# P-LED-0004-V1A_EAGLE_Schematic.net
KiCad netlist of a schematic drawn in EAGLE
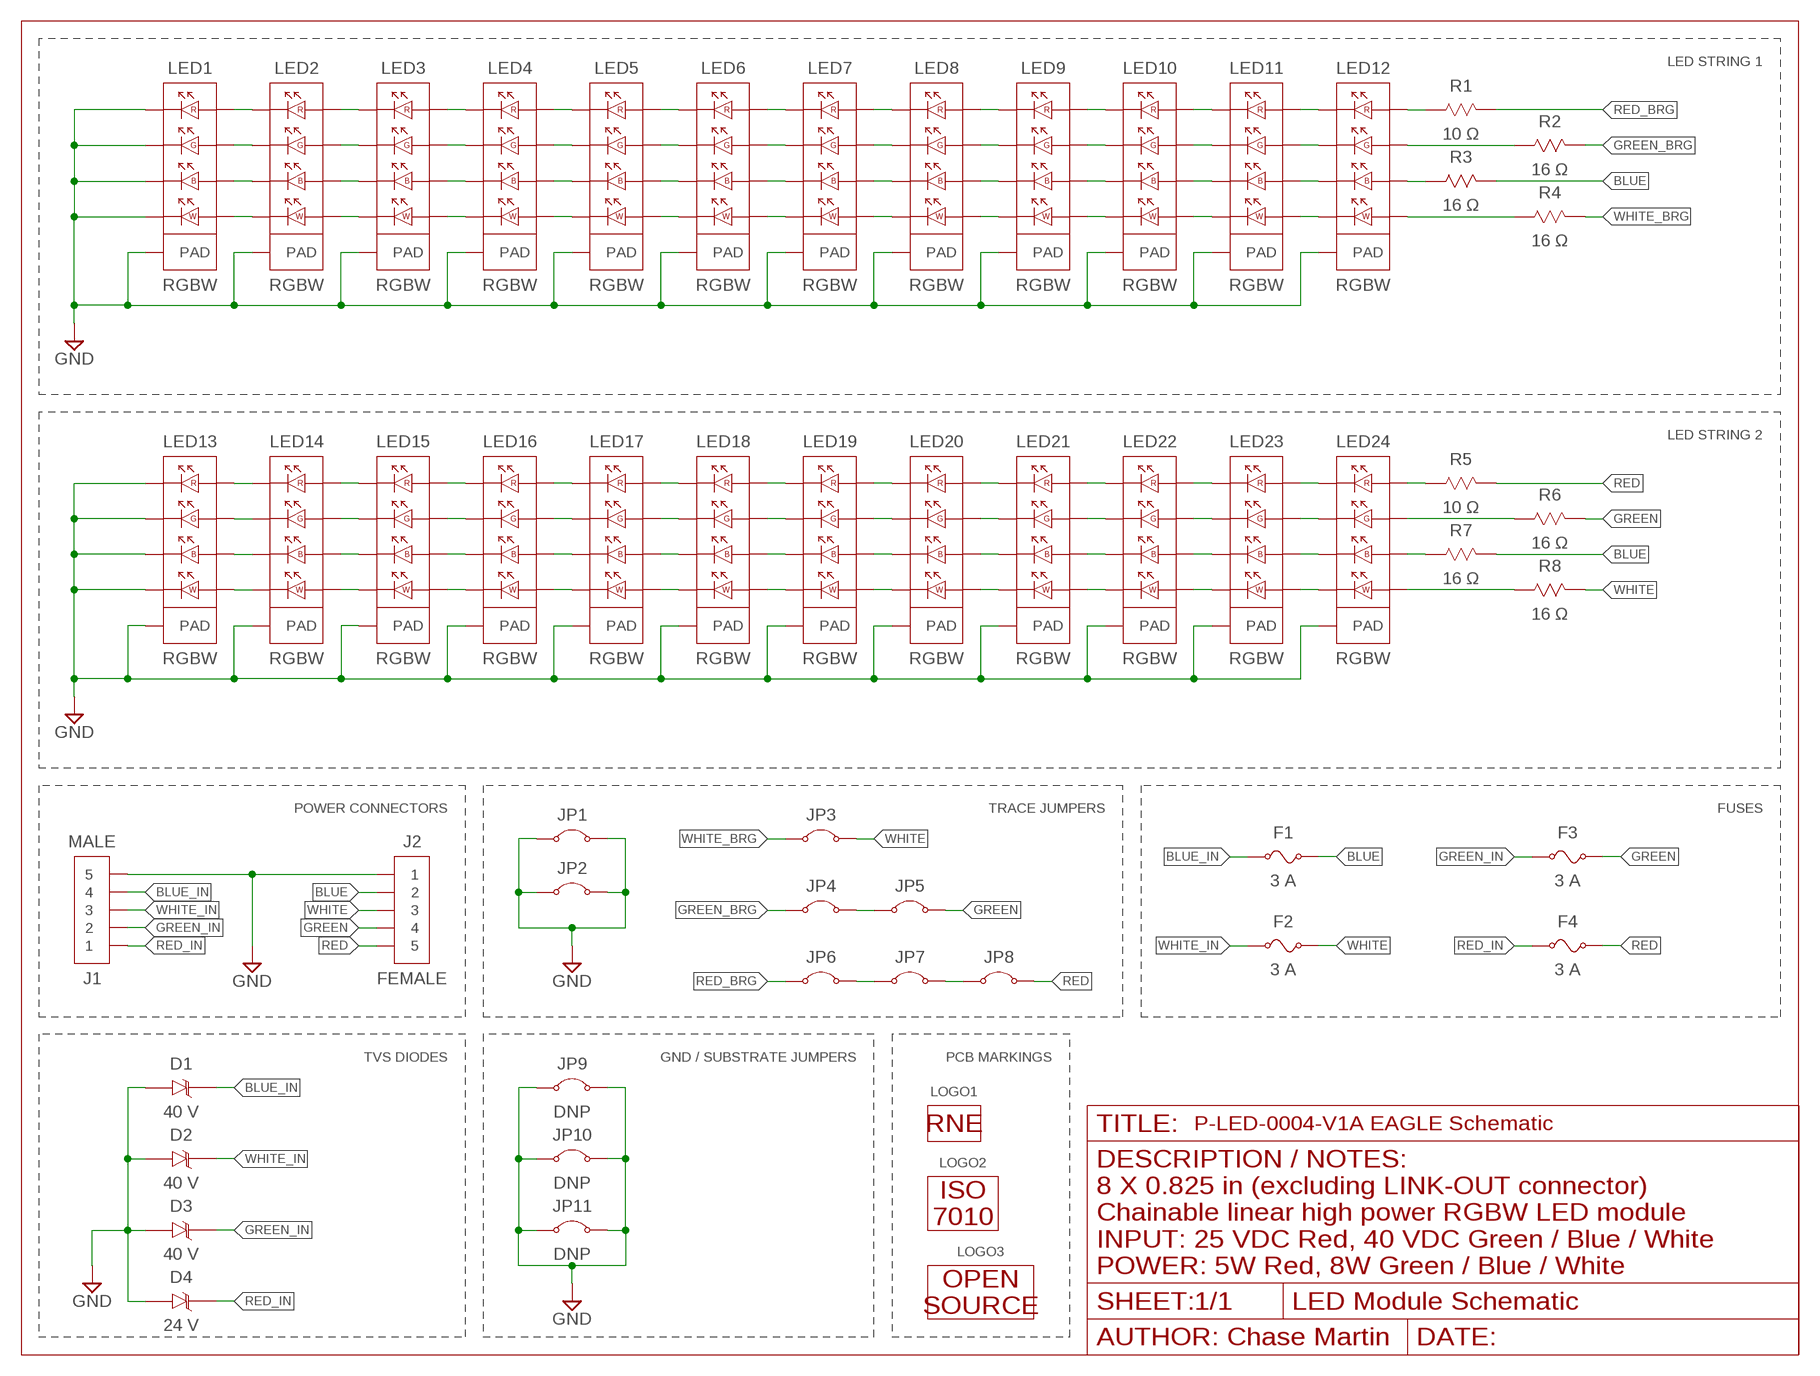
[diagram p0: schematic, sheet 1]

(export (version "E")
  (design (tool "Eeschema 10.0.6"))
  (components
    (comp (ref "D1")
      (value "40 V")
      (footprint "eagle-import:0603_POLARIZED")
      (libsource (lib "eagle-import") (part "UNIDIRECTIONAL_TVS_DIODESMD_0603"))
    )
    (comp (ref "D2")
      (value "40 V")
      (footprint "eagle-import:0603_POLARIZED")
      (libsource (lib "eagle-import") (part "UNIDIRECTIONAL_TVS_DIODESMD_0603"))
    )
    (comp (ref "D3")
      (value "40 V")
      (footprint "eagle-import:0603_POLARIZED")
      (libsource (lib "eagle-import") (part "UNIDIRECTIONAL_TVS_DIODESMD_0603"))
    )
    (comp (ref "D4")
      (value "24 V")
      (footprint "eagle-import:0603_POLARIZED")
      (libsource (lib "eagle-import") (part "UNIDIRECTIONAL_TVS_DIODESMD_0603"))
    )
    (comp (ref "F1")
      (value "3 A")
      (footprint "eagle-import:1206")
      (libsource (lib "eagle-import") (part "FUSESMD_1206"))
    )
    (comp (ref "F2")
      (value "3 A")
      (footprint "eagle-import:1206")
      (libsource (lib "eagle-import") (part "FUSESMD_1206"))
    )
    (comp (ref "F3")
      (value "3 A")
      (footprint "eagle-import:1206")
      (libsource (lib "eagle-import") (part "FUSESMD_1206"))
    )
    (comp (ref "F4")
      (value "3 A")
      (footprint "eagle-import:1206")
      (libsource (lib "eagle-import") (part "FUSESMD_1206"))
    )
    (comp (ref "J1")
      (value "MALE")
      (footprint "eagle-import:5-PIN_1-ROW_MALE_SMD_HORIZONTAL")
      (libsource (lib "eagle-import") (part "5-PIN_1-ROWMALE_SMD_HORIZONTAL"))
    )
    (comp (ref "J2")
      (value "FEMALE")
      (footprint "eagle-import:5-PIN_1-ROW_FEMALE_SMD_HORIZONTAL")
      (libsource (lib "eagle-import") (part "5-PIN_1-ROWFEMALE_SMD_HORIZONTAL"))
    )
    (comp (ref "JP1")
      (value "JUMPERSMD_1206")
      (footprint "eagle-import:1206")
      (libsource (lib "eagle-import") (part "JUMPERSMD_1206"))
    )
    (comp (ref "JP2")
      (value "JUMPERSMD_1206")
      (footprint "eagle-import:1206")
      (libsource (lib "eagle-import") (part "JUMPERSMD_1206"))
    )
    (comp (ref "JP3")
      (value "JUMPERSMD_1206")
      (footprint "eagle-import:1206")
      (libsource (lib "eagle-import") (part "JUMPERSMD_1206"))
    )
    (comp (ref "JP4")
      (value "JUMPERSMD_1206")
      (footprint "eagle-import:1206")
      (libsource (lib "eagle-import") (part "JUMPERSMD_1206"))
    )
    (comp (ref "JP5")
      (value "JUMPERSMD_1206")
      (footprint "eagle-import:1206")
      (libsource (lib "eagle-import") (part "JUMPERSMD_1206"))
    )
    (comp (ref "JP6")
      (value "JUMPERSMD_1206")
      (footprint "eagle-import:1206")
      (libsource (lib "eagle-import") (part "JUMPERSMD_1206"))
    )
    (comp (ref "JP7")
      (value "JUMPERSMD_1206")
      (footprint "eagle-import:1206")
      (libsource (lib "eagle-import") (part "JUMPERSMD_1206"))
    )
    (comp (ref "JP8")
      (value "JUMPERSMD_1206")
      (footprint "eagle-import:1206")
      (libsource (lib "eagle-import") (part "JUMPERSMD_1206"))
    )
    (comp (ref "JP9")
      (value "DNP")
      (footprint "eagle-import:0603")
      (libsource (lib "eagle-import") (part "JUMPERSMD_0603"))
    )
    (comp (ref "JP10")
      (value "DNP")
      (footprint "eagle-import:0603")
      (libsource (lib "eagle-import") (part "JUMPERSMD_0603"))
    )
    (comp (ref "JP11")
      (value "DNP")
      (footprint "eagle-import:0603")
      (libsource (lib "eagle-import") (part "JUMPERSMD_0603"))
    )
    (comp (ref "LED1")
      (value "RGBW")
      (footprint "eagle-import:IN-P55QSTGRGBW_AIS")
      (libsource (lib "eagle-import") (part "IN-P55QSTGRGBWAIS"))
    )
    (comp (ref "LED2")
      (value "RGBW")
      (footprint "eagle-import:IN-P55QSTGRGBW_AIS")
      (libsource (lib "eagle-import") (part "IN-P55QSTGRGBWAIS"))
    )
    (comp (ref "LED3")
      (value "RGBW")
      (footprint "eagle-import:IN-P55QSTGRGBW_AIS")
      (libsource (lib "eagle-import") (part "IN-P55QSTGRGBWAIS"))
    )
    (comp (ref "LED4")
      (value "RGBW")
      (footprint "eagle-import:IN-P55QSTGRGBW_AIS")
      (libsource (lib "eagle-import") (part "IN-P55QSTGRGBWAIS"))
    )
    (comp (ref "LED5")
      (value "RGBW")
      (footprint "eagle-import:IN-P55QSTGRGBW_AIS")
      (libsource (lib "eagle-import") (part "IN-P55QSTGRGBWAIS"))
    )
    (comp (ref "LED6")
      (value "RGBW")
      (footprint "eagle-import:IN-P55QSTGRGBW_AIS")
      (libsource (lib "eagle-import") (part "IN-P55QSTGRGBWAIS"))
    )
    (comp (ref "LED7")
      (value "RGBW")
      (footprint "eagle-import:IN-P55QSTGRGBW_AIS")
      (libsource (lib "eagle-import") (part "IN-P55QSTGRGBWAIS"))
    )
    (comp (ref "LED8")
      (value "RGBW")
      (footprint "eagle-import:IN-P55QSTGRGBW_AIS")
      (libsource (lib "eagle-import") (part "IN-P55QSTGRGBWAIS"))
    )
    (comp (ref "LED9")
      (value "RGBW")
      (footprint "eagle-import:IN-P55QSTGRGBW_AIS")
      (libsource (lib "eagle-import") (part "IN-P55QSTGRGBWAIS"))
    )
    (comp (ref "LED10")
      (value "RGBW")
      (footprint "eagle-import:IN-P55QSTGRGBW_AIS")
      (libsource (lib "eagle-import") (part "IN-P55QSTGRGBWAIS"))
    )
    (comp (ref "LED11")
      (value "RGBW")
      (footprint "eagle-import:IN-P55QSTGRGBW_AIS")
      (libsource (lib "eagle-import") (part "IN-P55QSTGRGBWAIS"))
    )
    (comp (ref "LED12")
      (value "RGBW")
      (footprint "eagle-import:IN-P55QSTGRGBW_AIS")
      (libsource (lib "eagle-import") (part "IN-P55QSTGRGBWAIS"))
    )
    (comp (ref "LED13")
      (value "RGBW")
      (footprint "eagle-import:IN-P55QSTGRGBW_AIS")
      (libsource (lib "eagle-import") (part "IN-P55QSTGRGBWAIS"))
    )
    (comp (ref "LED14")
      (value "RGBW")
      (footprint "eagle-import:IN-P55QSTGRGBW_AIS")
      (libsource (lib "eagle-import") (part "IN-P55QSTGRGBWAIS"))
    )
    (comp (ref "LED15")
      (value "RGBW")
      (footprint "eagle-import:IN-P55QSTGRGBW_AIS")
      (libsource (lib "eagle-import") (part "IN-P55QSTGRGBWAIS"))
    )
    (comp (ref "LED16")
      (value "RGBW")
      (footprint "eagle-import:IN-P55QSTGRGBW_AIS")
      (libsource (lib "eagle-import") (part "IN-P55QSTGRGBWAIS"))
    )
    (comp (ref "LED17")
      (value "RGBW")
      (footprint "eagle-import:IN-P55QSTGRGBW_AIS")
      (libsource (lib "eagle-import") (part "IN-P55QSTGRGBWAIS"))
    )
    (comp (ref "LED18")
      (value "RGBW")
      (footprint "eagle-import:IN-P55QSTGRGBW_AIS")
      (libsource (lib "eagle-import") (part "IN-P55QSTGRGBWAIS"))
    )
    (comp (ref "LED19")
      (value "RGBW")
      (footprint "eagle-import:IN-P55QSTGRGBW_AIS")
      (libsource (lib "eagle-import") (part "IN-P55QSTGRGBWAIS"))
    )
    (comp (ref "LED20")
      (value "RGBW")
      (footprint "eagle-import:IN-P55QSTGRGBW_AIS")
      (libsource (lib "eagle-import") (part "IN-P55QSTGRGBWAIS"))
    )
    (comp (ref "LED21")
      (value "RGBW")
      (footprint "eagle-import:IN-P55QSTGRGBW_AIS")
      (libsource (lib "eagle-import") (part "IN-P55QSTGRGBWAIS"))
    )
    (comp (ref "LED22")
      (value "RGBW")
      (footprint "eagle-import:IN-P55QSTGRGBW_AIS")
      (libsource (lib "eagle-import") (part "IN-P55QSTGRGBWAIS"))
    )
    (comp (ref "LED23")
      (value "RGBW")
      (footprint "eagle-import:IN-P55QSTGRGBW_AIS")
      (libsource (lib "eagle-import") (part "IN-P55QSTGRGBWAIS"))
    )
    (comp (ref "LED24")
      (value "RGBW")
      (footprint "eagle-import:IN-P55QSTGRGBW_AIS")
      (libsource (lib "eagle-import") (part "IN-P55QSTGRGBWAIS"))
    )
    (comp (ref "LOGO1")
      (value "PROFILE_LOGO_RNE0.375\"")
      (footprint "eagle-import:RNE_PROFILE-LOGO_375")
      (libsource (lib "eagle-import") (part "PROFILE_LOGO_RNE0.375{dblquote}"))
    )
    (comp (ref "LOGO2")
      (value "HOT_SURFACE_ISO0.375\"_LABEL")
      (footprint "eagle-import:ISO_HOT-SURFACE_375_LABEL")
      (libsource (lib "eagle-import") (part "HOT_SURFACE_ISO0.375{dblquote}_LABEL"))
    )
    (comp (ref "LOGO3")
      (value "OPEN_SOURCE_OSHWA0.375\"_LABEL")
      (footprint "eagle-import:OSHWA_OPEN-SOURCE_375_LABEL")
      (libsource (lib "eagle-import") (part "OPEN_SOURCE_OSHWA0.375{dblquote}_LABEL"))
    )
    (comp (ref "R1")
      (value "10 Ω")
      (footprint "eagle-import:0603")
      (libsource (lib "eagle-import") (part "RESISTORSMD_0603"))
    )
    (comp (ref "R2")
      (value "16 Ω")
      (footprint "eagle-import:0603")
      (libsource (lib "eagle-import") (part "RESISTORSMD_0603"))
    )
    (comp (ref "R3")
      (value "16 Ω")
      (footprint "eagle-import:0603")
      (libsource (lib "eagle-import") (part "RESISTORSMD_0603"))
    )
    (comp (ref "R4")
      (value "16 Ω")
      (footprint "eagle-import:0603")
      (libsource (lib "eagle-import") (part "RESISTORSMD_0603"))
    )
    (comp (ref "R5")
      (value "10 Ω")
      (footprint "eagle-import:0603")
      (libsource (lib "eagle-import") (part "RESISTORSMD_0603"))
    )
    (comp (ref "R6")
      (value "16 Ω")
      (footprint "eagle-import:0603")
      (libsource (lib "eagle-import") (part "RESISTORSMD_0603"))
    )
    (comp (ref "R7")
      (value "16 Ω")
      (footprint "eagle-import:0603")
      (libsource (lib "eagle-import") (part "RESISTORSMD_0603"))
    )
    (comp (ref "R8")
      (value "16 Ω")
      (footprint "eagle-import:0603")
      (libsource (lib "eagle-import") (part "RESISTORSMD_0603"))
    )
  )
  (nets
    (net (code "1") (name "BLUE") (class "Default")
      (node (ref "F1") (pin "2") (pinfunction "2_2") (pintype "passive"))
      (node (ref "J2") (pin "2") (pinfunction "2_2") (pintype "passive"))
      (node (ref "R3") (pin "2") (pinfunction "2_2") (pintype "passive"))
      (node (ref "R7") (pin "2") (pinfunction "2_2") (pintype "passive"))
    )
    (net (code "2") (name "BLUE_IN") (class "Default")
      (node (ref "D1") (pin "K") (pinfunction "K_K") (pintype "passive"))
      (node (ref "F1") (pin "1") (pinfunction "1_1") (pintype "passive"))
      (node (ref "J1") (pin "4") (pinfunction "4_4") (pintype "passive"))
    )
    (net (code "3") (name "GND") (class "Default")
      (node (ref "D1") (pin "A") (pinfunction "A_A") (pintype "passive"))
      (node (ref "D2") (pin "A") (pinfunction "A_A") (pintype "passive"))
      (node (ref "D3") (pin "A") (pinfunction "A_A") (pintype "passive"))
      (node (ref "D4") (pin "A") (pinfunction "A_A") (pintype "passive"))
      (node (ref "J1") (pin "5") (pinfunction "5_5") (pintype "passive"))
      (node (ref "J2") (pin "1") (pinfunction "1_1") (pintype "passive"))
      (node (ref "JP1") (pin "1") (pinfunction "1_1") (pintype "passive"))
      (node (ref "JP1") (pin "2") (pinfunction "2_2") (pintype "passive"))
      (node (ref "JP10") (pin "1") (pinfunction "1_1") (pintype "passive"))
      (node (ref "JP10") (pin "2") (pinfunction "2_2") (pintype "passive"))
      (node (ref "JP11") (pin "1") (pinfunction "1_1") (pintype "passive"))
      (node (ref "JP11") (pin "2") (pinfunction "2_2") (pintype "passive"))
      (node (ref "JP2") (pin "1") (pinfunction "1_1") (pintype "passive"))
      (node (ref "JP2") (pin "2") (pinfunction "2_2") (pintype "passive"))
      (node (ref "JP9") (pin "1") (pinfunction "1_1") (pintype "passive"))
      (node (ref "JP9") (pin "2") (pinfunction "2_2") (pintype "passive"))
      (node (ref "LED1") (pin "BLUE_N") (pinfunction "BLUE_N_BLUE_N") (pintype "output"))
      (node (ref "LED1") (pin "GREEN_N") (pinfunction "GREEN_N_GREEN_N") (pintype "output"))
      (node (ref "LED1") (pin "PAD") (pinfunction "PAD_PAD") (pintype "passive"))
      (node (ref "LED1") (pin "RED_N") (pinfunction "RED_N_RED_N") (pintype "output"))
      (node (ref "LED1") (pin "WHITE_N") (pinfunction "WHITE_N_WHITE_N") (pintype "output"))
      (node (ref "LED10") (pin "PAD") (pinfunction "PAD_PAD") (pintype "passive"))
      (node (ref "LED11") (pin "PAD") (pinfunction "PAD_PAD") (pintype "passive"))
      (node (ref "LED12") (pin "PAD") (pinfunction "PAD_PAD") (pintype "passive"))
      (node (ref "LED13") (pin "BLUE_N") (pinfunction "BLUE_N_BLUE_N") (pintype "output"))
      (node (ref "LED13") (pin "GREEN_N") (pinfunction "GREEN_N_GREEN_N") (pintype "output"))
      (node (ref "LED13") (pin "PAD") (pinfunction "PAD_PAD") (pintype "passive"))
      (node (ref "LED13") (pin "RED_N") (pinfunction "RED_N_RED_N") (pintype "output"))
      (node (ref "LED13") (pin "WHITE_N") (pinfunction "WHITE_N_WHITE_N") (pintype "output"))
      (node (ref "LED14") (pin "PAD") (pinfunction "PAD_PAD") (pintype "passive"))
      (node (ref "LED15") (pin "PAD") (pinfunction "PAD_PAD") (pintype "passive"))
      (node (ref "LED16") (pin "PAD") (pinfunction "PAD_PAD") (pintype "passive"))
      (node (ref "LED17") (pin "PAD") (pinfunction "PAD_PAD") (pintype "passive"))
      (node (ref "LED18") (pin "PAD") (pinfunction "PAD_PAD") (pintype "passive"))
      (node (ref "LED19") (pin "PAD") (pinfunction "PAD_PAD") (pintype "passive"))
      (node (ref "LED2") (pin "PAD") (pinfunction "PAD_PAD") (pintype "passive"))
      (node (ref "LED20") (pin "PAD") (pinfunction "PAD_PAD") (pintype "passive"))
      (node (ref "LED21") (pin "PAD") (pinfunction "PAD_PAD") (pintype "passive"))
      (node (ref "LED22") (pin "PAD") (pinfunction "PAD_PAD") (pintype "passive"))
      (node (ref "LED23") (pin "PAD") (pinfunction "PAD_PAD") (pintype "passive"))
      (node (ref "LED24") (pin "PAD") (pinfunction "PAD_PAD") (pintype "passive"))
      (node (ref "LED3") (pin "PAD") (pinfunction "PAD_PAD") (pintype "passive"))
      (node (ref "LED4") (pin "PAD") (pinfunction "PAD_PAD") (pintype "passive"))
      (node (ref "LED5") (pin "PAD") (pinfunction "PAD_PAD") (pintype "passive"))
      (node (ref "LED6") (pin "PAD") (pinfunction "PAD_PAD") (pintype "passive"))
      (node (ref "LED7") (pin "PAD") (pinfunction "PAD_PAD") (pintype "passive"))
      (node (ref "LED8") (pin "PAD") (pinfunction "PAD_PAD") (pintype "passive"))
      (node (ref "LED9") (pin "PAD") (pinfunction "PAD_PAD") (pintype "passive"))
    )
    (net (code "4") (name "GREEN") (class "Default")
      (node (ref "F3") (pin "2") (pinfunction "2_2") (pintype "passive"))
      (node (ref "J2") (pin "4") (pinfunction "4_4") (pintype "passive"))
      (node (ref "JP5") (pin "2") (pinfunction "2_2") (pintype "passive"))
      (node (ref "R6") (pin "2") (pinfunction "2_2") (pintype "passive"))
    )
    (net (code "5") (name "GREEN_BRG") (class "Default")
      (node (ref "JP4") (pin "1") (pinfunction "1_1") (pintype "passive"))
      (node (ref "R2") (pin "2") (pinfunction "2_2") (pintype "passive"))
    )
    (net (code "6") (name "GREEN_IN") (class "Default")
      (node (ref "D3") (pin "K") (pinfunction "K_K") (pintype "passive"))
      (node (ref "F3") (pin "1") (pinfunction "1_1") (pintype "passive"))
      (node (ref "J1") (pin "2") (pinfunction "2_2") (pintype "passive"))
    )
    (net (code "7") (name "Net-(JP4-Pad2)") (class "Default")
      (node (ref "JP4") (pin "2") (pinfunction "2_2") (pintype "passive"))
      (node (ref "JP5") (pin "1") (pinfunction "1_1") (pintype "passive"))
    )
    (net (code "8") (name "Net-(JP6-Pad2)") (class "Default")
      (node (ref "JP6") (pin "2") (pinfunction "2_2") (pintype "passive"))
      (node (ref "JP7") (pin "1") (pinfunction "1_1") (pintype "passive"))
    )
    (net (code "9") (name "Net-(JP7-Pad2)") (class "Default")
      (node (ref "JP7") (pin "2") (pinfunction "2_2") (pintype "passive"))
      (node (ref "JP8") (pin "1") (pinfunction "1_1") (pintype "passive"))
    )
    (net (code "10") (name "Net-(LED1-PadBLUE_P)") (class "Default")
      (node (ref "LED1") (pin "BLUE_P") (pinfunction "BLUE_P_BLUE_P") (pintype "input"))
      (node (ref "LED2") (pin "BLUE_N") (pinfunction "BLUE_N_BLUE_N") (pintype "output"))
    )
    (net (code "11") (name "Net-(LED1-PadGREEN_P)") (class "Default")
      (node (ref "LED1") (pin "GREEN_P") (pinfunction "GREEN_P_GREEN_P") (pintype "input"))
      (node (ref "LED2") (pin "GREEN_N") (pinfunction "GREEN_N_GREEN_N") (pintype "output"))
    )
    (net (code "12") (name "Net-(LED1-PadRED_P)") (class "Default")
      (node (ref "LED1") (pin "RED_P") (pinfunction "RED_P_RED_P") (pintype "input"))
      (node (ref "LED2") (pin "RED_N") (pinfunction "RED_N_RED_N") (pintype "output"))
    )
    (net (code "13") (name "Net-(LED1-PadWHITE_P)") (class "Default")
      (node (ref "LED1") (pin "WHITE_P") (pinfunction "WHITE_P_WHITE_P") (pintype "input"))
      (node (ref "LED2") (pin "WHITE_N") (pinfunction "WHITE_N_WHITE_N") (pintype "output"))
    )
    (net (code "14") (name "Net-(LED2-PadBLUE_P)") (class "Default")
      (node (ref "LED2") (pin "BLUE_P") (pinfunction "BLUE_P_BLUE_P") (pintype "input"))
      (node (ref "LED3") (pin "BLUE_N") (pinfunction "BLUE_N_BLUE_N") (pintype "output"))
    )
    (net (code "15") (name "Net-(LED2-PadGREEN_P)") (class "Default")
      (node (ref "LED2") (pin "GREEN_P") (pinfunction "GREEN_P_GREEN_P") (pintype "input"))
      (node (ref "LED3") (pin "GREEN_N") (pinfunction "GREEN_N_GREEN_N") (pintype "output"))
    )
    (net (code "16") (name "Net-(LED2-PadRED_P)") (class "Default")
      (node (ref "LED2") (pin "RED_P") (pinfunction "RED_P_RED_P") (pintype "input"))
      (node (ref "LED3") (pin "RED_N") (pinfunction "RED_N_RED_N") (pintype "output"))
    )
    (net (code "17") (name "Net-(LED2-PadWHITE_P)") (class "Default")
      (node (ref "LED2") (pin "WHITE_P") (pinfunction "WHITE_P_WHITE_P") (pintype "input"))
      (node (ref "LED3") (pin "WHITE_N") (pinfunction "WHITE_N_WHITE_N") (pintype "output"))
    )
    (net (code "18") (name "Net-(LED3-PadBLUE_P)") (class "Default")
      (node (ref "LED3") (pin "BLUE_P") (pinfunction "BLUE_P_BLUE_P") (pintype "input"))
      (node (ref "LED4") (pin "BLUE_N") (pinfunction "BLUE_N_BLUE_N") (pintype "output"))
    )
    (net (code "19") (name "Net-(LED3-PadGREEN_P)") (class "Default")
      (node (ref "LED3") (pin "GREEN_P") (pinfunction "GREEN_P_GREEN_P") (pintype "input"))
      (node (ref "LED4") (pin "GREEN_N") (pinfunction "GREEN_N_GREEN_N") (pintype "output"))
    )
    (net (code "20") (name "Net-(LED3-PadRED_P)") (class "Default")
      (node (ref "LED3") (pin "RED_P") (pinfunction "RED_P_RED_P") (pintype "input"))
      (node (ref "LED4") (pin "RED_N") (pinfunction "RED_N_RED_N") (pintype "output"))
    )
    (net (code "21") (name "Net-(LED3-PadWHITE_P)") (class "Default")
      (node (ref "LED3") (pin "WHITE_P") (pinfunction "WHITE_P_WHITE_P") (pintype "input"))
      (node (ref "LED4") (pin "WHITE_N") (pinfunction "WHITE_N_WHITE_N") (pintype "output"))
    )
    (net (code "22") (name "Net-(LED4-PadBLUE_P)") (class "Default")
      (node (ref "LED4") (pin "BLUE_P") (pinfunction "BLUE_P_BLUE_P") (pintype "input"))
      (node (ref "LED5") (pin "BLUE_N") (pinfunction "BLUE_N_BLUE_N") (pintype "output"))
    )
    (net (code "23") (name "Net-(LED4-PadGREEN_P)") (class "Default")
      (node (ref "LED4") (pin "GREEN_P") (pinfunction "GREEN_P_GREEN_P") (pintype "input"))
      (node (ref "LED5") (pin "GREEN_N") (pinfunction "GREEN_N_GREEN_N") (pintype "output"))
    )
    (net (code "24") (name "Net-(LED4-PadRED_P)") (class "Default")
      (node (ref "LED4") (pin "RED_P") (pinfunction "RED_P_RED_P") (pintype "input"))
      (node (ref "LED5") (pin "RED_N") (pinfunction "RED_N_RED_N") (pintype "output"))
    )
    (net (code "25") (name "Net-(LED4-PadWHITE_P)") (class "Default")
      (node (ref "LED4") (pin "WHITE_P") (pinfunction "WHITE_P_WHITE_P") (pintype "input"))
      (node (ref "LED5") (pin "WHITE_N") (pinfunction "WHITE_N_WHITE_N") (pintype "output"))
    )
    (net (code "26") (name "Net-(LED5-PadBLUE_P)") (class "Default")
      (node (ref "LED5") (pin "BLUE_P") (pinfunction "BLUE_P_BLUE_P") (pintype "input"))
      (node (ref "LED6") (pin "BLUE_N") (pinfunction "BLUE_N_BLUE_N") (pintype "output"))
    )
    (net (code "27") (name "Net-(LED5-PadGREEN_P)") (class "Default")
      (node (ref "LED5") (pin "GREEN_P") (pinfunction "GREEN_P_GREEN_P") (pintype "input"))
      (node (ref "LED6") (pin "GREEN_N") (pinfunction "GREEN_N_GREEN_N") (pintype "output"))
    )
    (net (code "28") (name "Net-(LED5-PadRED_P)") (class "Default")
      (node (ref "LED5") (pin "RED_P") (pinfunction "RED_P_RED_P") (pintype "input"))
      (node (ref "LED6") (pin "RED_N") (pinfunction "RED_N_RED_N") (pintype "output"))
    )
    (net (code "29") (name "Net-(LED5-PadWHITE_P)") (class "Default")
      (node (ref "LED5") (pin "WHITE_P") (pinfunction "WHITE_P_WHITE_P") (pintype "input"))
      (node (ref "LED6") (pin "WHITE_N") (pinfunction "WHITE_N_WHITE_N") (pintype "output"))
    )
    (net (code "30") (name "Net-(LED6-PadBLUE_P)") (class "Default")
      (node (ref "LED6") (pin "BLUE_P") (pinfunction "BLUE_P_BLUE_P") (pintype "input"))
      (node (ref "LED7") (pin "BLUE_N") (pinfunction "BLUE_N_BLUE_N") (pintype "output"))
    )
    (net (code "31") (name "Net-(LED6-PadGREEN_P)") (class "Default")
      (node (ref "LED6") (pin "GREEN_P") (pinfunction "GREEN_P_GREEN_P") (pintype "input"))
      (node (ref "LED7") (pin "GREEN_N") (pinfunction "GREEN_N_GREEN_N") (pintype "output"))
    )
    (net (code "32") (name "Net-(LED6-PadRED_P)") (class "Default")
      (node (ref "LED6") (pin "RED_P") (pinfunction "RED_P_RED_P") (pintype "input"))
      (node (ref "LED7") (pin "RED_N") (pinfunction "RED_N_RED_N") (pintype "output"))
    )
    (net (code "33") (name "Net-(LED6-PadWHITE_P)") (class "Default")
      (node (ref "LED6") (pin "WHITE_P") (pinfunction "WHITE_P_WHITE_P") (pintype "input"))
      (node (ref "LED7") (pin "WHITE_N") (pinfunction "WHITE_N_WHITE_N") (pintype "output"))
    )
    (net (code "34") (name "Net-(LED7-PadBLUE_P)") (class "Default")
      (node (ref "LED7") (pin "BLUE_P") (pinfunction "BLUE_P_BLUE_P") (pintype "input"))
      (node (ref "LED8") (pin "BLUE_N") (pinfunction "BLUE_N_BLUE_N") (pintype "output"))
    )
    (net (code "35") (name "Net-(LED7-PadGREEN_P)") (class "Default")
      (node (ref "LED7") (pin "GREEN_P") (pinfunction "GREEN_P_GREEN_P") (pintype "input"))
      (node (ref "LED8") (pin "GREEN_N") (pinfunction "GREEN_N_GREEN_N") (pintype "output"))
    )
    (net (code "36") (name "Net-(LED7-PadRED_P)") (class "Default")
      (node (ref "LED7") (pin "RED_P") (pinfunction "RED_P_RED_P") (pintype "input"))
      (node (ref "LED8") (pin "RED_N") (pinfunction "RED_N_RED_N") (pintype "output"))
    )
    (net (code "37") (name "Net-(LED7-PadWHITE_P)") (class "Default")
      (node (ref "LED7") (pin "WHITE_P") (pinfunction "WHITE_P_WHITE_P") (pintype "input"))
      (node (ref "LED8") (pin "WHITE_N") (pinfunction "WHITE_N_WHITE_N") (pintype "output"))
    )
    (net (code "38") (name "Net-(LED8-PadBLUE_P)") (class "Default")
      (node (ref "LED8") (pin "BLUE_P") (pinfunction "BLUE_P_BLUE_P") (pintype "input"))
      (node (ref "LED9") (pin "BLUE_N") (pinfunction "BLUE_N_BLUE_N") (pintype "output"))
    )
    (net (code "39") (name "Net-(LED8-PadGREEN_P)") (class "Default")
      (node (ref "LED8") (pin "GREEN_P") (pinfunction "GREEN_P_GREEN_P") (pintype "input"))
      (node (ref "LED9") (pin "GREEN_N") (pinfunction "GREEN_N_GREEN_N") (pintype "output"))
    )
    (net (code "40") (name "Net-(LED8-PadRED_P)") (class "Default")
      (node (ref "LED8") (pin "RED_P") (pinfunction "RED_P_RED_P") (pintype "input"))
      (node (ref "LED9") (pin "RED_N") (pinfunction "RED_N_RED_N") (pintype "output"))
    )
    (net (code "41") (name "Net-(LED8-PadWHITE_P)") (class "Default")
      (node (ref "LED8") (pin "WHITE_P") (pinfunction "WHITE_P_WHITE_P") (pintype "input"))
      (node (ref "LED9") (pin "WHITE_N") (pinfunction "WHITE_N_WHITE_N") (pintype "output"))
    )
    (net (code "42") (name "Net-(LED10-PadBLUE_N)") (class "Default")
      (node (ref "LED10") (pin "BLUE_N") (pinfunction "BLUE_N_BLUE_N") (pintype "output"))
      (node (ref "LED9") (pin "BLUE_P") (pinfunction "BLUE_P_BLUE_P") (pintype "input"))
    )
    (net (code "43") (name "Net-(LED10-PadBLUE_P)") (class "Default")
      (node (ref "LED10") (pin "BLUE_P") (pinfunction "BLUE_P_BLUE_P") (pintype "input"))
      (node (ref "LED11") (pin "BLUE_N") (pinfunction "BLUE_N_BLUE_N") (pintype "output"))
    )
    (net (code "44") (name "Net-(LED10-PadGREEN_N)") (class "Default")
      (node (ref "LED10") (pin "GREEN_N") (pinfunction "GREEN_N_GREEN_N") (pintype "output"))
      (node (ref "LED9") (pin "GREEN_P") (pinfunction "GREEN_P_GREEN_P") (pintype "input"))
    )
    (net (code "45") (name "Net-(LED10-PadGREEN_P)") (class "Default")
      (node (ref "LED10") (pin "GREEN_P") (pinfunction "GREEN_P_GREEN_P") (pintype "input"))
      (node (ref "LED11") (pin "GREEN_N") (pinfunction "GREEN_N_GREEN_N") (pintype "output"))
    )
    (net (code "46") (name "Net-(LED10-PadRED_N)") (class "Default")
      (node (ref "LED10") (pin "RED_N") (pinfunction "RED_N_RED_N") (pintype "output"))
      (node (ref "LED9") (pin "RED_P") (pinfunction "RED_P_RED_P") (pintype "input"))
    )
    (net (code "47") (name "Net-(LED10-PadRED_P)") (class "Default")
      (node (ref "LED10") (pin "RED_P") (pinfunction "RED_P_RED_P") (pintype "input"))
      (node (ref "LED11") (pin "RED_N") (pinfunction "RED_N_RED_N") (pintype "output"))
    )
    (net (code "48") (name "Net-(LED10-PadWHITE_N)") (class "Default")
      (node (ref "LED10") (pin "WHITE_N") (pinfunction "WHITE_N_WHITE_N") (pintype "output"))
      (node (ref "LED9") (pin "WHITE_P") (pinfunction "WHITE_P_WHITE_P") (pintype "input"))
    )
    (net (code "49") (name "Net-(LED10-PadWHITE_P)") (class "Default")
      (node (ref "LED10") (pin "WHITE_P") (pinfunction "WHITE_P_WHITE_P") (pintype "input"))
      (node (ref "LED11") (pin "WHITE_N") (pinfunction "WHITE_N_WHITE_N") (pintype "output"))
    )
    (net (code "50") (name "Net-(LED11-PadBLUE_P)") (class "Default")
      (node (ref "LED11") (pin "BLUE_P") (pinfunction "BLUE_P_BLUE_P") (pintype "input"))
      (node (ref "LED12") (pin "BLUE_N") (pinfunction "BLUE_N_BLUE_N") (pintype "output"))
    )
    (net (code "51") (name "Net-(LED11-PadGREEN_P)") (class "Default")
      (node (ref "LED11") (pin "GREEN_P") (pinfunction "GREEN_P_GREEN_P") (pintype "input"))
      (node (ref "LED12") (pin "GREEN_N") (pinfunction "GREEN_N_GREEN_N") (pintype "output"))
    )
    (net (code "52") (name "Net-(LED11-PadRED_P)") (class "Default")
      (node (ref "LED11") (pin "RED_P") (pinfunction "RED_P_RED_P") (pintype "input"))
      (node (ref "LED12") (pin "RED_N") (pinfunction "RED_N_RED_N") (pintype "output"))
    )
    (net (code "53") (name "Net-(LED11-PadWHITE_P)") (class "Default")
      (node (ref "LED11") (pin "WHITE_P") (pinfunction "WHITE_P_WHITE_P") (pintype "input"))
      (node (ref "LED12") (pin "WHITE_N") (pinfunction "WHITE_N_WHITE_N") (pintype "output"))
    )
    (net (code "54") (name "Net-(LED12-PadBLUE_P)") (class "Default")
      (node (ref "LED12") (pin "BLUE_P") (pinfunction "BLUE_P_BLUE_P") (pintype "input"))
      (node (ref "R3") (pin "1") (pinfunction "1_1") (pintype "passive"))
    )
    (net (code "55") (name "Net-(LED12-PadGREEN_P)") (class "Default")
      (node (ref "LED12") (pin "GREEN_P") (pinfunction "GREEN_P_GREEN_P") (pintype "input"))
      (node (ref "R2") (pin "1") (pinfunction "1_1") (pintype "passive"))
    )
    (net (code "56") (name "Net-(LED12-PadRED_P)") (class "Default")
      (node (ref "LED12") (pin "RED_P") (pinfunction "RED_P_RED_P") (pintype "input"))
      (node (ref "R1") (pin "1") (pinfunction "1_1") (pintype "passive"))
    )
    (net (code "57") (name "Net-(LED12-PadWHITE_P)") (class "Default")
      (node (ref "LED12") (pin "WHITE_P") (pinfunction "WHITE_P_WHITE_P") (pintype "input"))
      (node (ref "R4") (pin "1") (pinfunction "1_1") (pintype "passive"))
    )
    (net (code "58") (name "Net-(LED13-PadBLUE_P)") (class "Default")
      (node (ref "LED13") (pin "BLUE_P") (pinfunction "BLUE_P_BLUE_P") (pintype "input"))
      (node (ref "LED14") (pin "BLUE_N") (pinfunction "BLUE_N_BLUE_N") (pintype "output"))
    )
    (net (code "59") (name "Net-(LED13-PadGREEN_P)") (class "Default")
      (node (ref "LED13") (pin "GREEN_P") (pinfunction "GREEN_P_GREEN_P") (pintype "input"))
      (node (ref "LED14") (pin "GREEN_N") (pinfunction "GREEN_N_GREEN_N") (pintype "output"))
    )
    (net (code "60") (name "Net-(LED13-PadRED_P)") (class "Default")
      (node (ref "LED13") (pin "RED_P") (pinfunction "RED_P_RED_P") (pintype "input"))
      (node (ref "LED14") (pin "RED_N") (pinfunction "RED_N_RED_N") (pintype "output"))
    )
    (net (code "61") (name "Net-(LED13-PadWHITE_P)") (class "Default")
      (node (ref "LED13") (pin "WHITE_P") (pinfunction "WHITE_P_WHITE_P") (pintype "input"))
      (node (ref "LED14") (pin "WHITE_N") (pinfunction "WHITE_N_WHITE_N") (pintype "output"))
    )
    (net (code "62") (name "Net-(LED14-PadBLUE_P)") (class "Default")
      (node (ref "LED14") (pin "BLUE_P") (pinfunction "BLUE_P_BLUE_P") (pintype "input"))
      (node (ref "LED15") (pin "BLUE_N") (pinfunction "BLUE_N_BLUE_N") (pintype "output"))
    )
    (net (code "63") (name "Net-(LED14-PadGREEN_P)") (class "Default")
      (node (ref "LED14") (pin "GREEN_P") (pinfunction "GREEN_P_GREEN_P") (pintype "input"))
      (node (ref "LED15") (pin "GREEN_N") (pinfunction "GREEN_N_GREEN_N") (pintype "output"))
    )
    (net (code "64") (name "Net-(LED14-PadRED_P)") (class "Default")
      (node (ref "LED14") (pin "RED_P") (pinfunction "RED_P_RED_P") (pintype "input"))
      (node (ref "LED15") (pin "RED_N") (pinfunction "RED_N_RED_N") (pintype "output"))
    )
    (net (code "65") (name "Net-(LED14-PadWHITE_P)") (class "Default")
      (node (ref "LED14") (pin "WHITE_P") (pinfunction "WHITE_P_WHITE_P") (pintype "input"))
      (node (ref "LED15") (pin "WHITE_N") (pinfunction "WHITE_N_WHITE_N") (pintype "output"))
    )
    (net (code "66") (name "Net-(LED15-PadBLUE_P)") (class "Default")
      (node (ref "LED15") (pin "BLUE_P") (pinfunction "BLUE_P_BLUE_P") (pintype "input"))
      (node (ref "LED16") (pin "BLUE_N") (pinfunction "BLUE_N_BLUE_N") (pintype "output"))
    )
    (net (code "67") (name "Net-(LED15-PadGREEN_P)") (class "Default")
      (node (ref "LED15") (pin "GREEN_P") (pinfunction "GREEN_P_GREEN_P") (pintype "input"))
      (node (ref "LED16") (pin "GREEN_N") (pinfunction "GREEN_N_GREEN_N") (pintype "output"))
    )
    (net (code "68") (name "Net-(LED15-PadRED_P)") (class "Default")
      (node (ref "LED15") (pin "RED_P") (pinfunction "RED_P_RED_P") (pintype "input"))
      (node (ref "LED16") (pin "RED_N") (pinfunction "RED_N_RED_N") (pintype "output"))
    )
    (net (code "69") (name "Net-(LED15-PadWHITE_P)") (class "Default")
      (node (ref "LED15") (pin "WHITE_P") (pinfunction "WHITE_P_WHITE_P") (pintype "input"))
      (node (ref "LED16") (pin "WHITE_N") (pinfunction "WHITE_N_WHITE_N") (pintype "output"))
    )
    (net (code "70") (name "Net-(LED16-PadBLUE_P)") (class "Default")
      (node (ref "LED16") (pin "BLUE_P") (pinfunction "BLUE_P_BLUE_P") (pintype "input"))
      (node (ref "LED17") (pin "BLUE_N") (pinfunction "BLUE_N_BLUE_N") (pintype "output"))
    )
    (net (code "71") (name "Net-(LED16-PadGREEN_P)") (class "Default")
      (node (ref "LED16") (pin "GREEN_P") (pinfunction "GREEN_P_GREEN_P") (pintype "input"))
      (node (ref "LED17") (pin "GREEN_N") (pinfunction "GREEN_N_GREEN_N") (pintype "output"))
    )
    (net (code "72") (name "Net-(LED16-PadRED_P)") (class "Default")
      (node (ref "LED16") (pin "RED_P") (pinfunction "RED_P_RED_P") (pintype "input"))
      (node (ref "LED17") (pin "RED_N") (pinfunction "RED_N_RED_N") (pintype "output"))
    )
    (net (code "73") (name "Net-(LED16-PadWHITE_P)") (class "Default")
      (node (ref "LED16") (pin "WHITE_P") (pinfunction "WHITE_P_WHITE_P") (pintype "input"))
      (node (ref "LED17") (pin "WHITE_N") (pinfunction "WHITE_N_WHITE_N") (pintype "output"))
    )
    (net (code "74") (name "Net-(LED17-PadBLUE_P)") (class "Default")
      (node (ref "LED17") (pin "BLUE_P") (pinfunction "BLUE_P_BLUE_P") (pintype "input"))
      (node (ref "LED18") (pin "BLUE_N") (pinfunction "BLUE_N_BLUE_N") (pintype "output"))
    )
    (net (code "75") (name "Net-(LED17-PadGREEN_P)") (class "Default")
      (node (ref "LED17") (pin "GREEN_P") (pinfunction "GREEN_P_GREEN_P") (pintype "input"))
      (node (ref "LED18") (pin "GREEN_N") (pinfunction "GREEN_N_GREEN_N") (pintype "output"))
    )
    (net (code "76") (name "Net-(LED17-PadRED_P)") (class "Default")
      (node (ref "LED17") (pin "RED_P") (pinfunction "RED_P_RED_P") (pintype "input"))
      (node (ref "LED18") (pin "RED_N") (pinfunction "RED_N_RED_N") (pintype "output"))
    )
    (net (code "77") (name "Net-(LED17-PadWHITE_P)") (class "Default")
      (node (ref "LED17") (pin "WHITE_P") (pinfunction "WHITE_P_WHITE_P") (pintype "input"))
      (node (ref "LED18") (pin "WHITE_N") (pinfunction "WHITE_N_WHITE_N") (pintype "output"))
    )
    (net (code "78") (name "Net-(LED18-PadBLUE_P)") (class "Default")
      (node (ref "LED18") (pin "BLUE_P") (pinfunction "BLUE_P_BLUE_P") (pintype "input"))
      (node (ref "LED19") (pin "BLUE_N") (pinfunction "BLUE_N_BLUE_N") (pintype "output"))
    )
    (net (code "79") (name "Net-(LED18-PadGREEN_P)") (class "Default")
      (node (ref "LED18") (pin "GREEN_P") (pinfunction "GREEN_P_GREEN_P") (pintype "input"))
      (node (ref "LED19") (pin "GREEN_N") (pinfunction "GREEN_N_GREEN_N") (pintype "output"))
    )
    (net (code "80") (name "Net-(LED18-PadRED_P)") (class "Default")
      (node (ref "LED18") (pin "RED_P") (pinfunction "RED_P_RED_P") (pintype "input"))
      (node (ref "LED19") (pin "RED_N") (pinfunction "RED_N_RED_N") (pintype "output"))
    )
    (net (code "81") (name "Net-(LED18-PadWHITE_P)") (class "Default")
      (node (ref "LED18") (pin "WHITE_P") (pinfunction "WHITE_P_WHITE_P") (pintype "input"))
      (node (ref "LED19") (pin "WHITE_N") (pinfunction "WHITE_N_WHITE_N") (pintype "output"))
    )
    (net (code "82") (name "Net-(LED19-PadBLUE_P)") (class "Default")
      (node (ref "LED19") (pin "BLUE_P") (pinfunction "BLUE_P_BLUE_P") (pintype "input"))
      (node (ref "LED20") (pin "BLUE_N") (pinfunction "BLUE_N_BLUE_N") (pintype "output"))
    )
    (net (code "83") (name "Net-(LED19-PadGREEN_P)") (class "Default")
      (node (ref "LED19") (pin "GREEN_P") (pinfunction "GREEN_P_GREEN_P") (pintype "input"))
      (node (ref "LED20") (pin "GREEN_N") (pinfunction "GREEN_N_GREEN_N") (pintype "output"))
    )
    (net (code "84") (name "Net-(LED19-PadRED_P)") (class "Default")
      (node (ref "LED19") (pin "RED_P") (pinfunction "RED_P_RED_P") (pintype "input"))
      (node (ref "LED20") (pin "RED_N") (pinfunction "RED_N_RED_N") (pintype "output"))
    )
    (net (code "85") (name "Net-(LED19-PadWHITE_P)") (class "Default")
      (node (ref "LED19") (pin "WHITE_P") (pinfunction "WHITE_P_WHITE_P") (pintype "input"))
      (node (ref "LED20") (pin "WHITE_N") (pinfunction "WHITE_N_WHITE_N") (pintype "output"))
    )
    (net (code "86") (name "Net-(LED20-PadBLUE_P)") (class "Default")
      (node (ref "LED20") (pin "BLUE_P") (pinfunction "BLUE_P_BLUE_P") (pintype "input"))
      (node (ref "LED21") (pin "BLUE_N") (pinfunction "BLUE_N_BLUE_N") (pintype "output"))
    )
    (net (code "87") (name "Net-(LED20-PadGREEN_P)") (class "Default")
      (node (ref "LED20") (pin "GREEN_P") (pinfunction "GREEN_P_GREEN_P") (pintype "input"))
      (node (ref "LED21") (pin "GREEN_N") (pinfunction "GREEN_N_GREEN_N") (pintype "output"))
    )
    (net (code "88") (name "Net-(LED20-PadRED_P)") (class "Default")
      (node (ref "LED20") (pin "RED_P") (pinfunction "RED_P_RED_P") (pintype "input"))
      (node (ref "LED21") (pin "RED_N") (pinfunction "RED_N_RED_N") (pintype "output"))
    )
    (net (code "89") (name "Net-(LED20-PadWHITE_P)") (class "Default")
      (node (ref "LED20") (pin "WHITE_P") (pinfunction "WHITE_P_WHITE_P") (pintype "input"))
      (node (ref "LED21") (pin "WHITE_N") (pinfunction "WHITE_N_WHITE_N") (pintype "output"))
    )
    (net (code "90") (name "Net-(LED21-PadBLUE_P)") (class "Default")
      (node (ref "LED21") (pin "BLUE_P") (pinfunction "BLUE_P_BLUE_P") (pintype "input"))
      (node (ref "LED22") (pin "BLUE_N") (pinfunction "BLUE_N_BLUE_N") (pintype "output"))
    )
    (net (code "91") (name "Net-(LED21-PadGREEN_P)") (class "Default")
      (node (ref "LED21") (pin "GREEN_P") (pinfunction "GREEN_P_GREEN_P") (pintype "input"))
      (node (ref "LED22") (pin "GREEN_N") (pinfunction "GREEN_N_GREEN_N") (pintype "output"))
    )
    (net (code "92") (name "Net-(LED21-PadRED_P)") (class "Default")
      (node (ref "LED21") (pin "RED_P") (pinfunction "RED_P_RED_P") (pintype "input"))
      (node (ref "LED22") (pin "RED_N") (pinfunction "RED_N_RED_N") (pintype "output"))
    )
    (net (code "93") (name "Net-(LED21-PadWHITE_P)") (class "Default")
      (node (ref "LED21") (pin "WHITE_P") (pinfunction "WHITE_P_WHITE_P") (pintype "input"))
      (node (ref "LED22") (pin "WHITE_N") (pinfunction "WHITE_N_WHITE_N") (pintype "output"))
    )
    (net (code "94") (name "Net-(LED22-PadBLUE_P)") (class "Default")
      (node (ref "LED22") (pin "BLUE_P") (pinfunction "BLUE_P_BLUE_P") (pintype "input"))
      (node (ref "LED23") (pin "BLUE_N") (pinfunction "BLUE_N_BLUE_N") (pintype "output"))
    )
    (net (code "95") (name "Net-(LED22-PadGREEN_P)") (class "Default")
      (node (ref "LED22") (pin "GREEN_P") (pinfunction "GREEN_P_GREEN_P") (pintype "input"))
      (node (ref "LED23") (pin "GREEN_N") (pinfunction "GREEN_N_GREEN_N") (pintype "output"))
    )
    (net (code "96") (name "Net-(LED22-PadRED_P)") (class "Default")
      (node (ref "LED22") (pin "RED_P") (pinfunction "RED_P_RED_P") (pintype "input"))
      (node (ref "LED23") (pin "RED_N") (pinfunction "RED_N_RED_N") (pintype "output"))
    )
    (net (code "97") (name "Net-(LED22-PadWHITE_P)") (class "Default")
      (node (ref "LED22") (pin "WHITE_P") (pinfunction "WHITE_P_WHITE_P") (pintype "input"))
      (node (ref "LED23") (pin "WHITE_N") (pinfunction "WHITE_N_WHITE_N") (pintype "output"))
    )
    (net (code "98") (name "Net-(LED23-PadBLUE_P)") (class "Default")
      (node (ref "LED23") (pin "BLUE_P") (pinfunction "BLUE_P_BLUE_P") (pintype "input"))
      (node (ref "LED24") (pin "BLUE_N") (pinfunction "BLUE_N_BLUE_N") (pintype "output"))
    )
    (net (code "99") (name "Net-(LED23-PadGREEN_P)") (class "Default")
      (node (ref "LED23") (pin "GREEN_P") (pinfunction "GREEN_P_GREEN_P") (pintype "input"))
      (node (ref "LED24") (pin "GREEN_N") (pinfunction "GREEN_N_GREEN_N") (pintype "output"))
    )
    (net (code "100") (name "Net-(LED23-PadRED_P)") (class "Default")
      (node (ref "LED23") (pin "RED_P") (pinfunction "RED_P_RED_P") (pintype "input"))
      (node (ref "LED24") (pin "RED_N") (pinfunction "RED_N_RED_N") (pintype "output"))
    )
    (net (code "101") (name "Net-(LED23-PadWHITE_P)") (class "Default")
      (node (ref "LED23") (pin "WHITE_P") (pinfunction "WHITE_P_WHITE_P") (pintype "input"))
      (node (ref "LED24") (pin "WHITE_N") (pinfunction "WHITE_N_WHITE_N") (pintype "output"))
    )
    (net (code "102") (name "Net-(LED24-PadBLUE_P)") (class "Default")
      (node (ref "LED24") (pin "BLUE_P") (pinfunction "BLUE_P_BLUE_P") (pintype "input"))
      (node (ref "R7") (pin "1") (pinfunction "1_1") (pintype "passive"))
    )
    (net (code "103") (name "Net-(LED24-PadGREEN_P)") (class "Default")
      (node (ref "LED24") (pin "GREEN_P") (pinfunction "GREEN_P_GREEN_P") (pintype "input"))
      (node (ref "R6") (pin "1") (pinfunction "1_1") (pintype "passive"))
    )
    (net (code "104") (name "Net-(LED24-PadRED_P)") (class "Default")
      (node (ref "LED24") (pin "RED_P") (pinfunction "RED_P_RED_P") (pintype "input"))
      (node (ref "R5") (pin "1") (pinfunction "1_1") (pintype "passive"))
    )
    (net (code "105") (name "Net-(LED24-PadWHITE_P)") (class "Default")
      (node (ref "LED24") (pin "WHITE_P") (pinfunction "WHITE_P_WHITE_P") (pintype "input"))
      (node (ref "R8") (pin "1") (pinfunction "1_1") (pintype "passive"))
    )
    (net (code "106") (name "RED") (class "Default")
      (node (ref "F4") (pin "2") (pinfunction "2_2") (pintype "passive"))
      (node (ref "J2") (pin "5") (pinfunction "5_5") (pintype "passive"))
      (node (ref "JP8") (pin "2") (pinfunction "2_2") (pintype "passive"))
      (node (ref "R5") (pin "2") (pinfunction "2_2") (pintype "passive"))
    )
    (net (code "107") (name "RED_BRG") (class "Default")
      (node (ref "JP6") (pin "1") (pinfunction "1_1") (pintype "passive"))
      (node (ref "R1") (pin "2") (pinfunction "2_2") (pintype "passive"))
    )
    (net (code "108") (name "RED_IN") (class "Default")
      (node (ref "D4") (pin "K") (pinfunction "K_K") (pintype "passive"))
      (node (ref "F4") (pin "1") (pinfunction "1_1") (pintype "passive"))
      (node (ref "J1") (pin "1") (pinfunction "1_1") (pintype "passive"))
    )
    (net (code "109") (name "WHITE") (class "Default")
      (node (ref "F2") (pin "2") (pinfunction "2_2") (pintype "passive"))
      (node (ref "J2") (pin "3") (pinfunction "3_3") (pintype "passive"))
      (node (ref "JP3") (pin "2") (pinfunction "2_2") (pintype "passive"))
      (node (ref "R8") (pin "2") (pinfunction "2_2") (pintype "passive"))
    )
    (net (code "110") (name "WHITE_BRG") (class "Default")
      (node (ref "JP3") (pin "1") (pinfunction "1_1") (pintype "passive"))
      (node (ref "R4") (pin "2") (pinfunction "2_2") (pintype "passive"))
    )
    (net (code "111") (name "WHITE_IN") (class "Default")
      (node (ref "D2") (pin "K") (pinfunction "K_K") (pintype "passive"))
      (node (ref "F2") (pin "1") (pinfunction "1_1") (pintype "passive"))
      (node (ref "J1") (pin "3") (pinfunction "3_3") (pintype "passive"))
    )
  )
)
